# LED6Channels.net
KiCad netlist of a schematic drawn in EAGLE
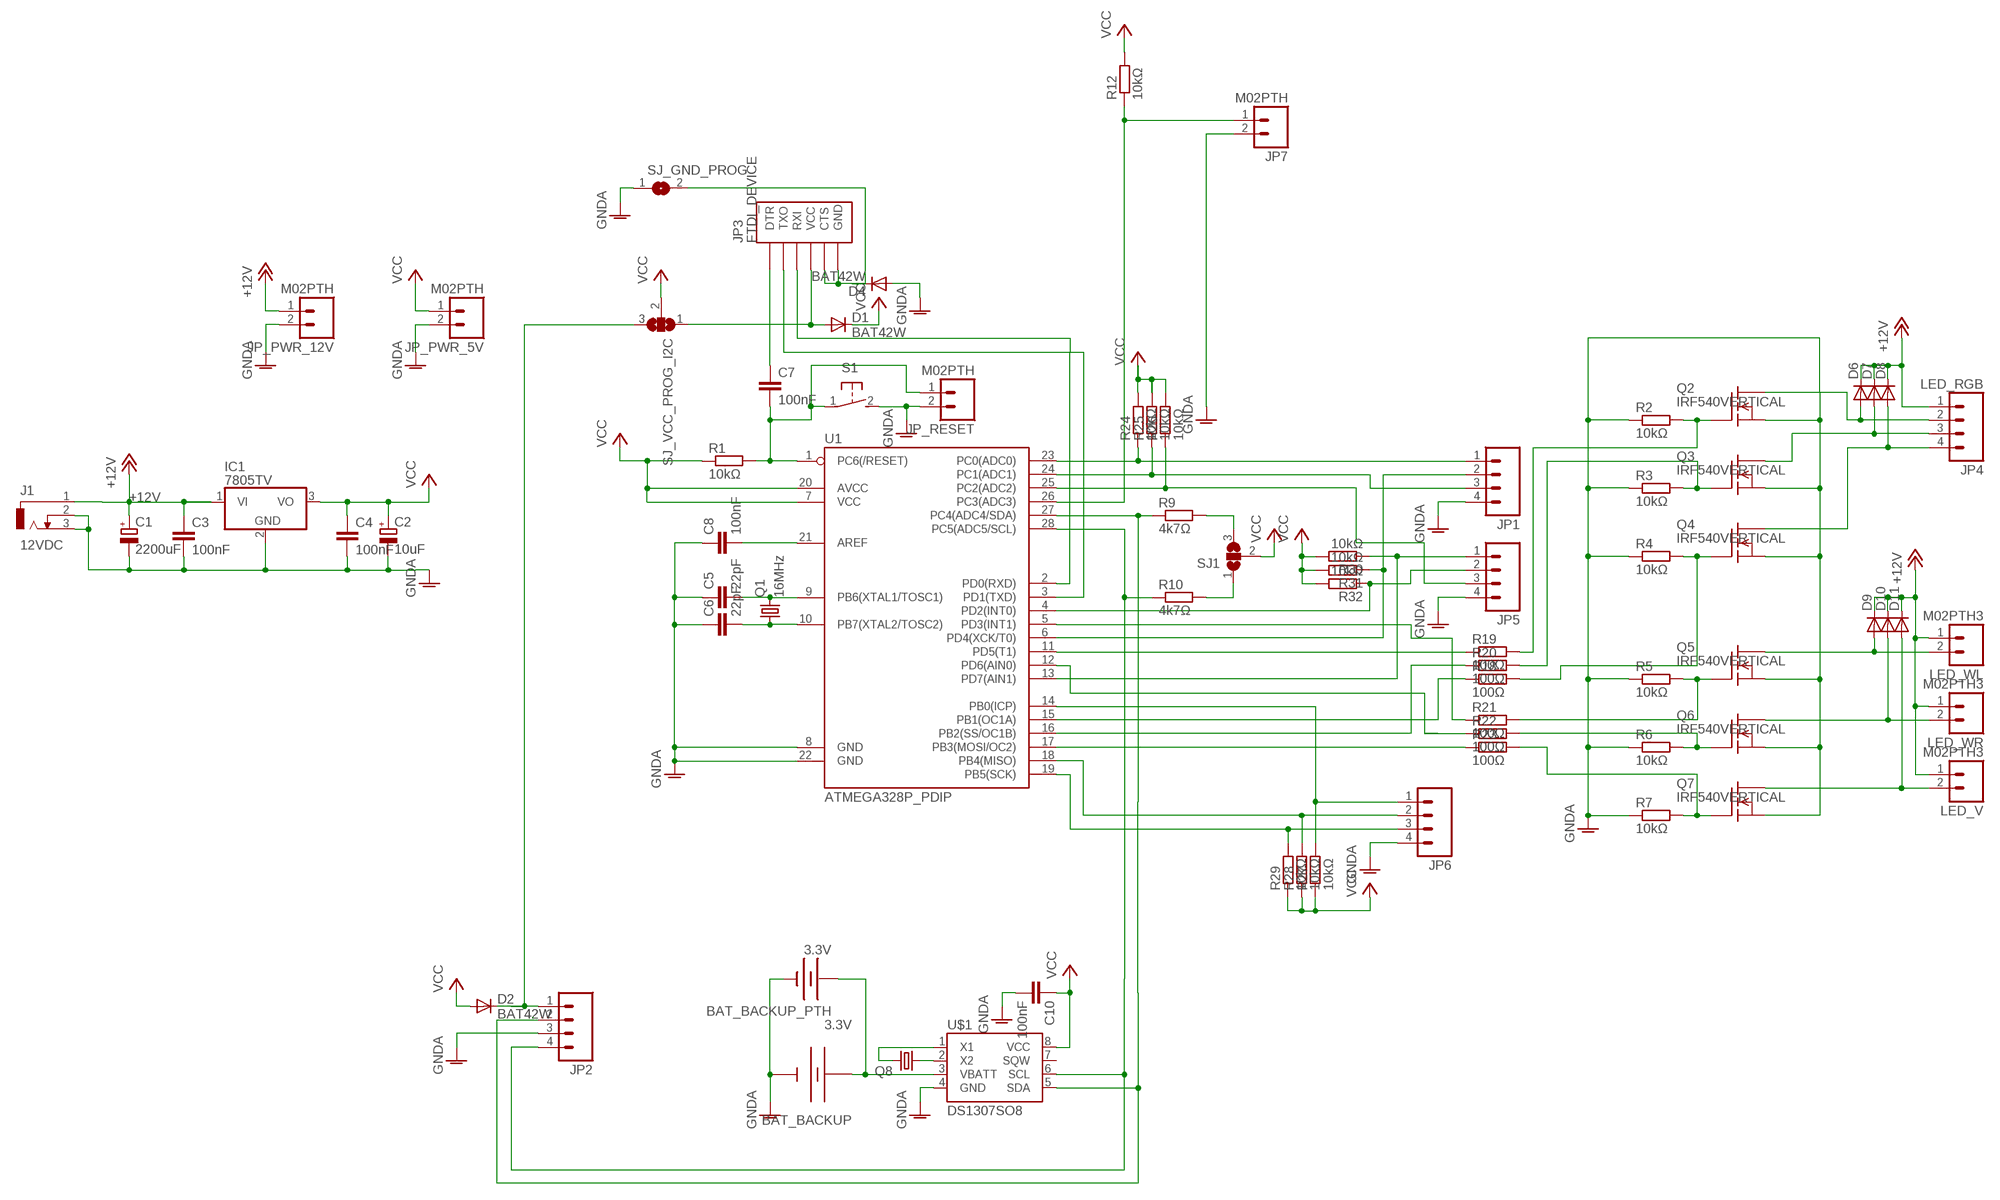
[diagram p0: schematic, sheet 1]

(export (version "E")
  (design (tool "Eeschema 10.0.6"))
  (components
    (comp (ref "BAT_BACKUP")
      (value "3.3V")
      (footprint "eagle-import:S8421-45R-NOVIAS")
      (libsource (lib "eagle-import") (part "BATTERYNOVIAS"))
    )
    (comp (ref "BAT_BACKUP_PTH")
      (value "3.3V")
      (footprint "eagle-import:BATTCOM_20MM_PTH")
      (libsource (lib "eagle-import") (part "BATTERY20PTH"))
    )
    (comp (ref "C1")
      (value "2200uF")
      (footprint "eagle-import:E5-13")
      (libsource (lib "eagle-import") (part "CPOL-EUE5-13"))
    )
    (comp (ref "C2")
      (value "10uF")
      (footprint "eagle-import:E2-5")
      (libsource (lib "eagle-import") (part "CPOL-EUE2-5"))
    )
    (comp (ref "C3")
      (value "100nF")
      (footprint "eagle-import:C025-024X044")
      (libsource (lib "eagle-import") (part "C-EU025-024X044"))
    )
    (comp (ref "C4")
      (value "100nF")
      (footprint "eagle-import:C025-024X044")
      (libsource (lib "eagle-import") (part "C-EU025-024X044"))
    )
    (comp (ref "C5")
      (value "22pF")
      (footprint "eagle-import:C025-024X044")
      (libsource (lib "eagle-import") (part "C-EU025-024X044"))
    )
    (comp (ref "C6")
      (value "22pF")
      (footprint "eagle-import:C025-024X044")
      (libsource (lib "eagle-import") (part "C-EU025-024X044"))
    )
    (comp (ref "C7")
      (value "100nF")
      (footprint "eagle-import:C025-024X044")
      (libsource (lib "eagle-import") (part "C-EU025-024X044"))
    )
    (comp (ref "C8")
      (value "100nF")
      (footprint "eagle-import:C025-024X044")
      (libsource (lib "eagle-import") (part "C-EU025-024X044"))
    )
    (comp (ref "C10")
      (value "100nF")
      (footprint "eagle-import:C025-024X044")
      (libsource (lib "eagle-import") (part "C-EU025-024X044"))
    )
    (comp (ref "D1")
      (value "BAT42W")
      (footprint "eagle-import:SOD123")
      (libsource (lib "eagle-import") (part "DIODE-SOD123"))
    )
    (comp (ref "D2")
      (value "BAT42W")
      (footprint "eagle-import:SOD123")
      (libsource (lib "eagle-import") (part "DIODE-SOD123"))
    )
    (comp (ref "D4")
      (value "BAT42W")
      (footprint "eagle-import:SOD123")
      (libsource (lib "eagle-import") (part "DIODE-SOD123"))
    )
    (comp (ref "D6")
      (value "DIODE-DO201-05V")
      (footprint "eagle-import:DO201AD-05V")
      (libsource (lib "eagle-import") (part "DIODE-DO201-05V"))
    )
    (comp (ref "D7")
      (value "DIODE-DO201-05V")
      (footprint "eagle-import:DO201AD-05V")
      (libsource (lib "eagle-import") (part "DIODE-DO201-05V"))
    )
    (comp (ref "D8")
      (value "DIODE-DO201-05V")
      (footprint "eagle-import:DO201AD-05V")
      (libsource (lib "eagle-import") (part "DIODE-DO201-05V"))
    )
    (comp (ref "D9")
      (value "DIODE-DO201-05V")
      (footprint "eagle-import:DO201AD-05V")
      (libsource (lib "eagle-import") (part "DIODE-DO201-05V"))
    )
    (comp (ref "D10")
      (value "DIODE-DO201-05V")
      (footprint "eagle-import:DO201AD-05V")
      (libsource (lib "eagle-import") (part "DIODE-DO201-05V"))
    )
    (comp (ref "D11")
      (value "DIODE-DO201-05V")
      (footprint "eagle-import:DO201AD-05V")
      (libsource (lib "eagle-import") (part "DIODE-DO201-05V"))
    )
    (comp (ref "IC1")
      (value "7805TV")
      (footprint "eagle-import:TO220V")
      (libsource (lib "eagle-import") (part "78TV05"))
    )
    (comp (ref "J1")
      (value "12VDC")
      (footprint "eagle-import:DCJ0303")
      (libsource (lib "eagle-import") (part "DCJ0303"))
    )
    (comp (ref "JP1")
      (value "M04LONGPADS")
      (footprint "eagle-import:1X04_LONGPADS")
      (libsource (lib "eagle-import") (part "M04LONGPADS"))
    )
    (comp (ref "JP2")
      (value "M04LONGPADS")
      (footprint "eagle-import:1X04_LONGPADS")
      (libsource (lib "eagle-import") (part "M04LONGPADS"))
    )
    (comp (ref "JP3")
      (value "FTDI_DEVICE")
      (footprint "eagle-import:FTDI_DEVICE_SIDE")
      (libsource (lib "eagle-import") (part "FTDI_DEVICE"))
    )
    (comp (ref "JP4")
      (value "LED_RGB")
      (footprint "eagle-import:1X04_LONGPADS")
      (libsource (lib "eagle-import") (part "M04LONGPADS"))
    )
    (comp (ref "JP5")
      (value "M04LONGPADS")
      (footprint "eagle-import:1X04_LONGPADS")
      (libsource (lib "eagle-import") (part "M04LONGPADS"))
    )
    (comp (ref "JP6")
      (value "M04LONGPADS")
      (footprint "eagle-import:1X04_LONGPADS")
      (libsource (lib "eagle-import") (part "M04LONGPADS"))
    )
    (comp (ref "JP7")
      (value "M02PTH")
      (footprint "eagle-import:1X02")
      (libsource (lib "eagle-import") (part "M02PTH"))
    )
    (comp (ref "JP_PWR_5V")
      (value "M02PTH")
      (footprint "eagle-import:1X02")
      (libsource (lib "eagle-import") (part "M02PTH"))
    )
    (comp (ref "JP_PWR_12V")
      (value "M02PTH")
      (footprint "eagle-import:1X02")
      (libsource (lib "eagle-import") (part "M02PTH"))
    )
    (comp (ref "JP_RESET")
      (value "M02PTH")
      (footprint "eagle-import:1X02")
      (libsource (lib "eagle-import") (part "M02PTH"))
    )
    (comp (ref "LED_V")
      (value "M02PTH3")
      (footprint "eagle-import:1X02_LONGPADS")
      (libsource (lib "eagle-import") (part "M02PTH3"))
    )
    (comp (ref "LED_WL")
      (value "M02PTH3")
      (footprint "eagle-import:1X02_LONGPADS")
      (libsource (lib "eagle-import") (part "M02PTH3"))
    )
    (comp (ref "LED_WR")
      (value "M02PTH3")
      (footprint "eagle-import:1X02_LONGPADS")
      (libsource (lib "eagle-import") (part "M02PTH3"))
    )
    (comp (ref "Q1")
      (value "16MHz")
      (footprint "eagle-import:HC49_S")
      (libsource (lib "eagle-import") (part "CRYSTALHC49S"))
    )
    (comp (ref "Q2")
      (value "IRF540VERTICAL")
      (footprint "eagle-import:TO220V")
      (libsource (lib "eagle-import") (part "IRF540VERTICAL"))
    )
    (comp (ref "Q3")
      (value "IRF540VERTICAL")
      (footprint "eagle-import:TO220V")
      (libsource (lib "eagle-import") (part "IRF540VERTICAL"))
    )
    (comp (ref "Q4")
      (value "IRF540VERTICAL")
      (footprint "eagle-import:TO220V")
      (libsource (lib "eagle-import") (part "IRF540VERTICAL"))
    )
    (comp (ref "Q5")
      (value "IRF540VERTICAL")
      (footprint "eagle-import:TO220V")
      (libsource (lib "eagle-import") (part "IRF540VERTICAL"))
    )
    (comp (ref "Q6")
      (value "IRF540VERTICAL")
      (footprint "eagle-import:TO220V")
      (libsource (lib "eagle-import") (part "IRF540VERTICAL"))
    )
    (comp (ref "Q7")
      (value "IRF540VERTICAL")
      (footprint "eagle-import:TO220V")
      (libsource (lib "eagle-import") (part "IRF540VERTICAL"))
    )
    (comp (ref "Q8")
      (value "CRYSTALTC26H")
      (footprint "eagle-import:TC26H")
      (libsource (lib "eagle-import") (part "CRYSTALTC26H"))
    )
    (comp (ref "R1")
      (value "10kΩ")
      (footprint "eagle-import:0207_10")
      (libsource (lib "eagle-import") (part "R-EU_0207/10"))
    )
    (comp (ref "R2")
      (value "10kΩ")
      (footprint "eagle-import:0207_10")
      (libsource (lib "eagle-import") (part "R-EU_0207/10"))
    )
    (comp (ref "R3")
      (value "10kΩ")
      (footprint "eagle-import:0207_10")
      (libsource (lib "eagle-import") (part "R-EU_0207/10"))
    )
    (comp (ref "R4")
      (value "10kΩ")
      (footprint "eagle-import:0207_10")
      (libsource (lib "eagle-import") (part "R-EU_0207/10"))
    )
    (comp (ref "R5")
      (value "10kΩ")
      (footprint "eagle-import:0207_10")
      (libsource (lib "eagle-import") (part "R-EU_0207/10"))
    )
    (comp (ref "R6")
      (value "10kΩ")
      (footprint "eagle-import:0207_10")
      (libsource (lib "eagle-import") (part "R-EU_0207/10"))
    )
    (comp (ref "R7")
      (value "10kΩ")
      (footprint "eagle-import:0207_10")
      (libsource (lib "eagle-import") (part "R-EU_0207/10"))
    )
    (comp (ref "R9")
      (value "4k7Ω")
      (footprint "eagle-import:0207_10")
      (libsource (lib "eagle-import") (part "R-EU_0207/10"))
    )
    (comp (ref "R10")
      (value "4k7Ω")
      (footprint "eagle-import:0207_10")
      (libsource (lib "eagle-import") (part "R-EU_0207/10"))
    )
    (comp (ref "R12")
      (value "10kΩ")
      (footprint "eagle-import:0207_10")
      (libsource (lib "eagle-import") (part "R-EU_0207/10"))
    )
    (comp (ref "R18")
      (value "100Ω")
      (footprint "eagle-import:0207_10")
      (libsource (lib "eagle-import") (part "R-EU_0207/10"))
    )
    (comp (ref "R19")
      (value "100Ω")
      (footprint "eagle-import:0207_10")
      (libsource (lib "eagle-import") (part "R-EU_0207/10"))
    )
    (comp (ref "R20")
      (value "100Ω")
      (footprint "eagle-import:0207_10")
      (libsource (lib "eagle-import") (part "R-EU_0207/10"))
    )
    (comp (ref "R21")
      (value "100Ω")
      (footprint "eagle-import:0207_10")
      (libsource (lib "eagle-import") (part "R-EU_0207/10"))
    )
    (comp (ref "R22")
      (value "100Ω")
      (footprint "eagle-import:0207_10")
      (libsource (lib "eagle-import") (part "R-EU_0207/10"))
    )
    (comp (ref "R23")
      (value "100Ω")
      (footprint "eagle-import:0207_10")
      (libsource (lib "eagle-import") (part "R-EU_0207/10"))
    )
    (comp (ref "R24")
      (value "10kΩ")
      (footprint "eagle-import:0207_10")
      (libsource (lib "eagle-import") (part "R-EU_0207/10"))
    )
    (comp (ref "R25")
      (value "10kΩ")
      (footprint "eagle-import:0207_10")
      (libsource (lib "eagle-import") (part "R-EU_0207/10"))
    )
    (comp (ref "R26")
      (value "10kΩ")
      (footprint "eagle-import:0207_10")
      (libsource (lib "eagle-import") (part "R-EU_0207/10"))
    )
    (comp (ref "R27")
      (value "10kΩ")
      (footprint "eagle-import:0207_10")
      (libsource (lib "eagle-import") (part "R-EU_0207/10"))
    )
    (comp (ref "R28")
      (value "10kΩ")
      (footprint "eagle-import:0207_10")
      (libsource (lib "eagle-import") (part "R-EU_0207/10"))
    )
    (comp (ref "R29")
      (value "10kΩ")
      (footprint "eagle-import:0207_10")
      (libsource (lib "eagle-import") (part "R-EU_0207/10"))
    )
    (comp (ref "R30")
      (value "10kΩ")
      (footprint "eagle-import:0207_10")
      (libsource (lib "eagle-import") (part "R-EU_0207/10"))
    )
    (comp (ref "R31")
      (value "10kΩ")
      (footprint "eagle-import:0207_10")
      (libsource (lib "eagle-import") (part "R-EU_0207/10"))
    )
    (comp (ref "R32")
      (value "10kΩ")
      (footprint "eagle-import:0207_10")
      (libsource (lib "eagle-import") (part "R-EU_0207/10"))
    )
    (comp (ref "S1")
      (value "31-XX")
      (footprint "eagle-import:B3F-31XX")
      (fields (field (name "MPN") "B3F-3100"))
      (libsource (lib "eagle-import") (part "31-XX"))
    )
    (comp (ref "SJ1")
      (value "SJ2W")
      (footprint "eagle-import:SJ_2")
      (libsource (lib "eagle-import") (part "SJ2W"))
    )
    (comp (ref "SJ_GND_PROG")
      (value "SJ")
      (footprint "eagle-import:SJ")
      (libsource (lib "eagle-import") (part "SJ"))
    )
    (comp (ref "SJ_VCC_PROG_I2C")
      (value "SJ2W")
      (footprint "eagle-import:SJ_2")
      (libsource (lib "eagle-import") (part "SJ2W"))
    )
    (comp (ref "U$1")
      (value "DS1307SO8")
      (footprint "eagle-import:SO08")
      (libsource (lib "eagle-import") (part "DS1307SO8"))
    )
    (comp (ref "U1")
      (value "ATMEGA328P_PDIP")
      (footprint "eagle-import:DIL28-3")
      (libsource (lib "eagle-import") (part "ATMEGA328P_PDIP"))
    )
  )
  (nets
    (net (code "1") (name "+12V") (class "Default")
      (node (ref "C1") (pin "+") (pinfunction "+_+") (pintype "passive"))
      (node (ref "C3") (pin "1") (pinfunction "1_1") (pintype "passive"))
      (node (ref "D10") (pin "C") (pinfunction "C_C") (pintype "passive"))
      (node (ref "D11") (pin "C") (pinfunction "C_C") (pintype "passive"))
      (node (ref "D6") (pin "C") (pinfunction "C_C") (pintype "passive"))
      (node (ref "D7") (pin "C") (pinfunction "C_C") (pintype "passive"))
      (node (ref "D8") (pin "C") (pinfunction "C_C") (pintype "passive"))
      (node (ref "D9") (pin "C") (pinfunction "C_C") (pintype "passive"))
      (node (ref "IC1") (pin "1") (pinfunction "VI_1") (pintype "input"))
      (node (ref "J1") (pin "1") (pinfunction "1_1") (pintype "passive"))
      (node (ref "JP4") (pin "1") (pinfunction "1_1") (pintype "passive"))
      (node (ref "JP_PWR_12V") (pin "1") (pinfunction "1_1") (pintype "passive"))
      (node (ref "LED_V") (pin "1") (pinfunction "1_1") (pintype "passive"))
      (node (ref "LED_WL") (pin "1") (pinfunction "1_1") (pintype "passive"))
      (node (ref "LED_WR") (pin "1") (pinfunction "1_1") (pintype "passive"))
    )
    (net (code "2") (name "GNDA") (class "Default")
      (node (ref "BAT_BACKUP") (pin "2") (pinfunction "-_2") (pintype "bidirectional"))
      (node (ref "BAT_BACKUP_PTH") (pin "2") (pinfunction "-_2") (pintype "power_in"))
      (node (ref "C1") (pin "-") (pinfunction "-_-") (pintype "passive"))
      (node (ref "C10") (pin "2") (pinfunction "2_2") (pintype "passive"))
      (node (ref "C2") (pin "-") (pinfunction "-_-") (pintype "passive"))
      (node (ref "C3") (pin "2") (pinfunction "2_2") (pintype "passive"))
      (node (ref "C4") (pin "2") (pinfunction "2_2") (pintype "passive"))
      (node (ref "C5") (pin "1") (pinfunction "1_1") (pintype "passive"))
      (node (ref "C6") (pin "1") (pinfunction "1_1") (pintype "passive"))
      (node (ref "C8") (pin "1") (pinfunction "1_1") (pintype "passive"))
      (node (ref "D4") (pin "A") (pinfunction "A_A") (pintype "passive"))
      (node (ref "IC1") (pin "2") (pinfunction "GND_2") (pintype "passive"))
      (node (ref "J1") (pin "2") (pinfunction "2_2") (pintype "passive"))
      (node (ref "J1") (pin "3") (pinfunction "3_3") (pintype "passive"))
      (node (ref "JP1") (pin "4") (pinfunction "4_4") (pintype "passive"))
      (node (ref "JP2") (pin "3") (pinfunction "3_3") (pintype "passive"))
      (node (ref "JP5") (pin "4") (pinfunction "4_4") (pintype "passive"))
      (node (ref "JP6") (pin "4") (pinfunction "4_4") (pintype "passive"))
      (node (ref "JP7") (pin "2") (pinfunction "2_2") (pintype "passive"))
      (node (ref "JP_PWR_12V") (pin "2") (pinfunction "2_2") (pintype "passive"))
      (node (ref "JP_PWR_5V") (pin "2") (pinfunction "2_2") (pintype "passive"))
      (node (ref "JP_RESET") (pin "2") (pinfunction "2_2") (pintype "passive"))
      (node (ref "Q2") (pin "3") (pinfunction "S_3") (pintype "passive"))
      (node (ref "Q3") (pin "3") (pinfunction "S_3") (pintype "passive"))
      (node (ref "Q4") (pin "3") (pinfunction "S_3") (pintype "passive"))
      (node (ref "Q5") (pin "3") (pinfunction "S_3") (pintype "passive"))
      (node (ref "Q6") (pin "3") (pinfunction "S_3") (pintype "passive"))
      (node (ref "Q7") (pin "3") (pinfunction "S_3") (pintype "passive"))
      (node (ref "R2") (pin "1") (pinfunction "1_1") (pintype "passive"))
      (node (ref "R3") (pin "1") (pinfunction "1_1") (pintype "passive"))
      (node (ref "R4") (pin "1") (pinfunction "1_1") (pintype "passive"))
      (node (ref "R5") (pin "1") (pinfunction "1_1") (pintype "passive"))
      (node (ref "R6") (pin "1") (pinfunction "1_1") (pintype "passive"))
      (node (ref "R7") (pin "1") (pinfunction "1_1") (pintype "passive"))
      (node (ref "S1") (pin "2") (pinfunction "S_2") (pintype "passive"))
      (node (ref "SJ_GND_PROG") (pin "1") (pinfunction "1_1") (pintype "passive"))
      (node (ref "U$1") (pin "4") (pinfunction "GND_4") (pintype "bidirectional"))
      (node (ref "U1") (pin "22") (pinfunction "GND_22") (pintype "bidirectional"))
      (node (ref "U1") (pin "8") (pinfunction "GND_8") (pintype "bidirectional"))
    )
    (net (code "3") (name "Net-(BAT_BACKUP-+)") (class "Default")
      (node (ref "BAT_BACKUP") (pin "1") (pinfunction "+_1") (pintype "bidirectional"))
      (node (ref "BAT_BACKUP_PTH") (pin "1") (pinfunction "+_1") (pintype "power_in"))
      (node (ref "U$1") (pin "3") (pinfunction "VBATT_3") (pintype "bidirectional"))
    )
    (net (code "4") (name "Net-(D2-PadC)") (class "Default")
      (node (ref "D2") (pin "C") (pinfunction "C_C") (pintype "passive"))
      (node (ref "JP2") (pin "1") (pinfunction "1_1") (pintype "passive"))
      (node (ref "SJ_VCC_PROG_I2C") (pin "3") (pinfunction "3_3") (pintype "passive"))
    )
    (net (code "5") (name "Net-(JP3-CTS)") (class "Default")
      (node (ref "D4") (pin "C") (pinfunction "C_C") (pintype "passive"))
      (node (ref "JP3") (pin "P$5") (pinfunction "CTS_P$5") (pintype "bidirectional"))
      (node (ref "JP3") (pin "P$6") (pinfunction "GND_P$6") (pintype "bidirectional"))
      (node (ref "SJ_GND_PROG") (pin "2") (pinfunction "2_2") (pintype "passive"))
    )
    (net (code "6") (name "Net-(JP3-DTR)") (class "Default")
      (node (ref "C7") (pin "1") (pinfunction "1_1") (pintype "passive"))
      (node (ref "JP3") (pin "P$1") (pinfunction "DTR_P$1") (pintype "bidirectional"))
    )
    (net (code "7") (name "Net-(JP3-RXI)") (class "Default")
      (node (ref "JP3") (pin "P$3") (pinfunction "RXI_P$3") (pintype "bidirectional"))
      (node (ref "U1") (pin "2") (pinfunction "PD0(RXD)_2") (pintype "bidirectional"))
    )
    (net (code "8") (name "Net-(JP3-TXO)") (class "Default")
      (node (ref "JP3") (pin "P$2") (pinfunction "TXO_P$2") (pintype "bidirectional"))
      (node (ref "U1") (pin "3") (pinfunction "PD1(TXD)_3") (pintype "bidirectional"))
    )
    (net (code "9") (name "Net-(JP3-VCC)") (class "Default")
      (node (ref "D1") (pin "A") (pinfunction "A_A") (pintype "passive"))
      (node (ref "JP3") (pin "P$4") (pinfunction "VCC_P$4") (pintype "bidirectional"))
      (node (ref "SJ_VCC_PROG_I2C") (pin "1") (pinfunction "1_1") (pintype "passive"))
    )
    (net (code "10") (name "Net-(Q2-D)") (class "Default")
      (node (ref "D6") (pin "A") (pinfunction "A_A") (pintype "passive"))
      (node (ref "JP4") (pin "2") (pinfunction "2_2") (pintype "passive"))
      (node (ref "Q2") (pin "2") (pinfunction "D_2") (pintype "passive"))
    )
    (net (code "11") (name "Net-(Q2-G)") (class "Default")
      (node (ref "Q2") (pin "1") (pinfunction "G_1") (pintype "passive"))
      (node (ref "R19") (pin "2") (pinfunction "2_2") (pintype "passive"))
      (node (ref "R2") (pin "2") (pinfunction "2_2") (pintype "passive"))
    )
    (net (code "12") (name "Net-(Q3-D)") (class "Default")
      (node (ref "D7") (pin "A") (pinfunction "A_A") (pintype "passive"))
      (node (ref "JP4") (pin "3") (pinfunction "3_3") (pintype "passive"))
      (node (ref "Q3") (pin "2") (pinfunction "D_2") (pintype "passive"))
    )
    (net (code "13") (name "Net-(Q3-G)") (class "Default")
      (node (ref "Q3") (pin "1") (pinfunction "G_1") (pintype "passive"))
      (node (ref "R20") (pin "2") (pinfunction "2_2") (pintype "passive"))
      (node (ref "R3") (pin "2") (pinfunction "2_2") (pintype "passive"))
    )
    (net (code "14") (name "Net-(Q4-D)") (class "Default")
      (node (ref "D8") (pin "A") (pinfunction "A_A") (pintype "passive"))
      (node (ref "JP4") (pin "4") (pinfunction "4_4") (pintype "passive"))
      (node (ref "Q4") (pin "2") (pinfunction "D_2") (pintype "passive"))
    )
    (net (code "15") (name "Net-(Q4-G)") (class "Default")
      (node (ref "Q4") (pin "1") (pinfunction "G_1") (pintype "passive"))
      (node (ref "R18") (pin "2") (pinfunction "2_2") (pintype "passive"))
      (node (ref "R4") (pin "2") (pinfunction "2_2") (pintype "passive"))
    )
    (net (code "16") (name "Net-(Q5-D)") (class "Default")
      (node (ref "D9") (pin "A") (pinfunction "A_A") (pintype "passive"))
      (node (ref "LED_WL") (pin "2") (pinfunction "2_2") (pintype "passive"))
      (node (ref "Q5") (pin "2") (pinfunction "D_2") (pintype "passive"))
    )
    (net (code "17") (name "Net-(Q5-G)") (class "Default")
      (node (ref "Q5") (pin "1") (pinfunction "G_1") (pintype "passive"))
      (node (ref "R21") (pin "2") (pinfunction "2_2") (pintype "passive"))
      (node (ref "R5") (pin "2") (pinfunction "2_2") (pintype "passive"))
    )
    (net (code "18") (name "Net-(Q6-D)") (class "Default")
      (node (ref "D10") (pin "A") (pinfunction "A_A") (pintype "passive"))
      (node (ref "LED_WR") (pin "2") (pinfunction "2_2") (pintype "passive"))
      (node (ref "Q6") (pin "2") (pinfunction "D_2") (pintype "passive"))
    )
    (net (code "19") (name "Net-(Q6-G)") (class "Default")
      (node (ref "Q6") (pin "1") (pinfunction "G_1") (pintype "passive"))
      (node (ref "R22") (pin "2") (pinfunction "2_2") (pintype "passive"))
      (node (ref "R6") (pin "2") (pinfunction "2_2") (pintype "passive"))
    )
    (net (code "20") (name "Net-(Q7-D)") (class "Default")
      (node (ref "D11") (pin "A") (pinfunction "A_A") (pintype "passive"))
      (node (ref "LED_V") (pin "2") (pinfunction "2_2") (pintype "passive"))
      (node (ref "Q7") (pin "2") (pinfunction "D_2") (pintype "passive"))
    )
    (net (code "21") (name "Net-(Q7-G)") (class "Default")
      (node (ref "Q7") (pin "1") (pinfunction "G_1") (pintype "passive"))
      (node (ref "R23") (pin "2") (pinfunction "2_2") (pintype "passive"))
      (node (ref "R7") (pin "2") (pinfunction "2_2") (pintype "passive"))
    )
    (net (code "22") (name "Net-(R9-Pad2)") (class "Default")
      (node (ref "R9") (pin "2") (pinfunction "2_2") (pintype "passive"))
      (node (ref "SJ1") (pin "3") (pinfunction "3_3") (pintype "passive"))
    )
    (net (code "23") (name "Net-(R10-Pad2)") (class "Default")
      (node (ref "R10") (pin "2") (pinfunction "2_2") (pintype "passive"))
      (node (ref "SJ1") (pin "1") (pinfunction "1_1") (pintype "passive"))
    )
    (net (code "24") (name "Net-(S1-P)") (class "Default")
      (node (ref "C7") (pin "2") (pinfunction "2_2") (pintype "passive"))
      (node (ref "JP_RESET") (pin "1") (pinfunction "1_1") (pintype "passive"))
      (node (ref "R1") (pin "2") (pinfunction "2_2") (pintype "passive"))
      (node (ref "S1") (pin "1") (pinfunction "P_1") (pintype "passive"))
      (node (ref "U1") (pin "1") (pinfunction "PC6(/RESET)_1") (pintype "bidirectional"))
    )
    (net (code "25") (name "Net-(U$1-SCL)") (class "Default")
      (node (ref "JP2") (pin "4") (pinfunction "4_4") (pintype "passive"))
      (node (ref "R10") (pin "1") (pinfunction "1_1") (pintype "passive"))
      (node (ref "U$1") (pin "6") (pinfunction "SCL_6") (pintype "bidirectional"))
      (node (ref "U1") (pin "28") (pinfunction "PC5(ADC5/SCL)_28") (pintype "bidirectional"))
    )
    (net (code "26") (name "Net-(U$1-SDA)") (class "Default")
      (node (ref "JP2") (pin "2") (pinfunction "2_2") (pintype "passive"))
      (node (ref "R9") (pin "1") (pinfunction "1_1") (pintype "passive"))
      (node (ref "U$1") (pin "5") (pinfunction "SDA_5") (pintype "bidirectional"))
      (node (ref "U1") (pin "27") (pinfunction "PC4(ADC4/SDA)_27") (pintype "bidirectional"))
    )
    (net (code "27") (name "Net-(U$1-X1)") (class "Default")
      (node (ref "Q8") (pin "2") (pinfunction "2_2") (pintype "passive"))
      (node (ref "U$1") (pin "1") (pinfunction "X1_1") (pintype "bidirectional"))
    )
    (net (code "28") (name "Net-(U$1-X2)") (class "Default")
      (node (ref "Q8") (pin "1") (pinfunction "1_1") (pintype "passive"))
      (node (ref "U$1") (pin "2") (pinfunction "X2_2") (pintype "bidirectional"))
    )
    (net (code "29") (name "Net-(U1-AREF)") (class "Default")
      (node (ref "C8") (pin "2") (pinfunction "2_2") (pintype "passive"))
      (node (ref "U1") (pin "21") (pinfunction "AREF_21") (pintype "bidirectional"))
    )
    (net (code "30") (name "Net-(U1-PB0(ICP))") (class "Default")
      (node (ref "JP6") (pin "1") (pinfunction "1_1") (pintype "passive"))
      (node (ref "R27") (pin "2") (pinfunction "2_2") (pintype "passive"))
      (node (ref "U1") (pin "14") (pinfunction "PB0(ICP)_14") (pintype "bidirectional"))
    )
    (net (code "31") (name "Net-(U1-PB1(OC1A))") (class "Default")
      (node (ref "R18") (pin "1") (pinfunction "1_1") (pintype "passive"))
      (node (ref "U1") (pin "15") (pinfunction "PB1(OC1A)_15") (pintype "bidirectional"))
    )
    (net (code "32") (name "Net-(U1-PB2(SS{slash}OC1B))") (class "Default")
      (node (ref "R20") (pin "1") (pinfunction "1_1") (pintype "passive"))
      (node (ref "U1") (pin "16") (pinfunction "PB2(SS/OC1B)_16") (pintype "bidirectional"))
    )
    (net (code "33") (name "Net-(U1-PB3(MOSI{slash}OC2))") (class "Default")
      (node (ref "R23") (pin "1") (pinfunction "1_1") (pintype "passive"))
      (node (ref "U1") (pin "17") (pinfunction "PB3(MOSI/OC2)_17") (pintype "bidirectional"))
    )
    (net (code "34") (name "Net-(U1-PB4(MISO))") (class "Default")
      (node (ref "JP6") (pin "2") (pinfunction "2_2") (pintype "passive"))
      (node (ref "R28") (pin "2") (pinfunction "2_2") (pintype "passive"))
      (node (ref "U1") (pin "18") (pinfunction "PB4(MISO)_18") (pintype "bidirectional"))
    )
    (net (code "35") (name "Net-(U1-PB5(SCK))") (class "Default")
      (node (ref "JP6") (pin "3") (pinfunction "3_3") (pintype "passive"))
      (node (ref "R29") (pin "2") (pinfunction "2_2") (pintype "passive"))
      (node (ref "U1") (pin "19") (pinfunction "PB5(SCK)_19") (pintype "bidirectional"))
    )
    (net (code "36") (name "Net-(U1-PB6(XTAL1{slash}TOSC1))") (class "Default")
      (node (ref "C5") (pin "2") (pinfunction "2_2") (pintype "passive"))
      (node (ref "Q1") (pin "2") (pinfunction "2_2") (pintype "passive"))
      (node (ref "U1") (pin "9") (pinfunction "PB6(XTAL1/TOSC1)_9") (pintype "bidirectional"))
    )
    (net (code "37") (name "Net-(U1-PB7(XTAL2{slash}TOSC2))") (class "Default")
      (node (ref "C6") (pin "2") (pinfunction "2_2") (pintype "passive"))
      (node (ref "Q1") (pin "1") (pinfunction "1_1") (pintype "passive"))
      (node (ref "U1") (pin "10") (pinfunction "PB7(XTAL2/TOSC2)_10") (pintype "bidirectional"))
    )
    (net (code "38") (name "Net-(U1-PC0(ADC0))") (class "Default")
      (node (ref "JP1") (pin "1") (pinfunction "1_1") (pintype "passive"))
      (node (ref "R24") (pin "1") (pinfunction "1_1") (pintype "passive"))
      (node (ref "U1") (pin "23") (pinfunction "PC0(ADC0)_23") (pintype "bidirectional"))
    )
    (net (code "39") (name "Net-(U1-PC1(ADC1))") (class "Default")
      (node (ref "JP1") (pin "3") (pinfunction "3_3") (pintype "passive"))
      (node (ref "R25") (pin "1") (pinfunction "1_1") (pintype "passive"))
      (node (ref "U1") (pin "24") (pinfunction "PC1(ADC1)_24") (pintype "bidirectional"))
    )
    (net (code "40") (name "Net-(U1-PC2(ADC2))") (class "Default")
      (node (ref "JP5") (pin "3") (pinfunction "3_3") (pintype "passive"))
      (node (ref "R26") (pin "1") (pinfunction "1_1") (pintype "passive"))
      (node (ref "U1") (pin "25") (pinfunction "PC2(ADC2)_25") (pintype "bidirectional"))
    )
    (net (code "41") (name "Net-(U1-PC3(ADC3))") (class "Default")
      (node (ref "JP7") (pin "1") (pinfunction "1_1") (pintype "passive"))
      (node (ref "R12") (pin "1") (pinfunction "1_1") (pintype "passive"))
      (node (ref "U1") (pin "26") (pinfunction "PC3(ADC3)_26") (pintype "bidirectional"))
    )
    (net (code "42") (name "Net-(U1-PD2(INT0))") (class "Default")
      (node (ref "JP5") (pin "2") (pinfunction "2_2") (pintype "passive"))
      (node (ref "R32") (pin "1") (pinfunction "1_1") (pintype "passive"))
      (node (ref "U1") (pin "4") (pinfunction "PD2(INT0)_4") (pintype "bidirectional"))
    )
    (net (code "43") (name "Net-(U1-PD3(INT1))") (class "Default")
      (node (ref "R21") (pin "1") (pinfunction "1_1") (pintype "passive"))
      (node (ref "U1") (pin "5") (pinfunction "PD3(INT1)_5") (pintype "bidirectional"))
    )
    (net (code "44") (name "Net-(U1-PD4(XCK{slash}T0))") (class "Default")
      (node (ref "JP1") (pin "2") (pinfunction "2_2") (pintype "passive"))
      (node (ref "R31") (pin "1") (pinfunction "1_1") (pintype "passive"))
      (node (ref "U1") (pin "6") (pinfunction "PD4(XCK/T0)_6") (pintype "bidirectional"))
    )
    (net (code "45") (name "Net-(U1-PD5(T1))") (class "Default")
      (node (ref "R19") (pin "1") (pinfunction "1_1") (pintype "passive"))
      (node (ref "U1") (pin "11") (pinfunction "PD5(T1)_11") (pintype "bidirectional"))
    )
    (net (code "46") (name "Net-(U1-PD6(AIN0))") (class "Default")
      (node (ref "R22") (pin "1") (pinfunction "1_1") (pintype "passive"))
      (node (ref "U1") (pin "12") (pinfunction "PD6(AIN0)_12") (pintype "bidirectional"))
    )
    (net (code "47") (name "Net-(U1-PD7(AIN1))") (class "Default")
      (node (ref "JP5") (pin "1") (pinfunction "1_1") (pintype "passive"))
      (node (ref "R30") (pin "1") (pinfunction "1_1") (pintype "passive"))
      (node (ref "U1") (pin "13") (pinfunction "PD7(AIN1)_13") (pintype "bidirectional"))
    )
    (net (code "48") (name "VCC") (class "Default")
      (node (ref "C10") (pin "1") (pinfunction "1_1") (pintype "passive"))
      (node (ref "C2") (pin "+") (pinfunction "+_+") (pintype "passive"))
      (node (ref "C4") (pin "1") (pinfunction "1_1") (pintype "passive"))
      (node (ref "D1") (pin "C") (pinfunction "C_C") (pintype "passive"))
      (node (ref "D2") (pin "A") (pinfunction "A_A") (pintype "passive"))
      (node (ref "IC1") (pin "3") (pinfunction "VO_3") (pintype "passive"))
      (node (ref "JP_PWR_5V") (pin "1") (pinfunction "1_1") (pintype "passive"))
      (node (ref "R1") (pin "1") (pinfunction "1_1") (pintype "passive"))
      (node (ref "R12") (pin "2") (pinfunction "2_2") (pintype "passive"))
      (node (ref "R24") (pin "2") (pinfunction "2_2") (pintype "passive"))
      (node (ref "R25") (pin "2") (pinfunction "2_2") (pintype "passive"))
      (node (ref "R26") (pin "2") (pinfunction "2_2") (pintype "passive"))
      (node (ref "R27") (pin "1") (pinfunction "1_1") (pintype "passive"))
      (node (ref "R28") (pin "1") (pinfunction "1_1") (pintype "passive"))
      (node (ref "R29") (pin "1") (pinfunction "1_1") (pintype "passive"))
      (node (ref "R30") (pin "2") (pinfunction "2_2") (pintype "passive"))
      (node (ref "R31") (pin "2") (pinfunction "2_2") (pintype "passive"))
      (node (ref "R32") (pin "2") (pinfunction "2_2") (pintype "passive"))
      (node (ref "SJ1") (pin "2") (pinfunction "2_2") (pintype "passive"))
      (node (ref "SJ_VCC_PROG_I2C") (pin "2") (pinfunction "2_2") (pintype "passive"))
      (node (ref "U$1") (pin "8") (pinfunction "VCC_8") (pintype "bidirectional"))
      (node (ref "U1") (pin "20") (pinfunction "AVCC_20") (pintype "bidirectional"))
      (node (ref "U1") (pin "7") (pinfunction "VCC_7") (pintype "bidirectional"))
    )
    (net (code "49") (name "unconnected-(U$1-SQW-Pad7)") (class "Default")
      (node (ref "U$1") (pin "7") (pinfunction "SQW_7") (pintype "bidirectional"))
    )
  )
)
